# icom_band_decoder.net
KiCad netlist of a schematic drawn in EAGLE
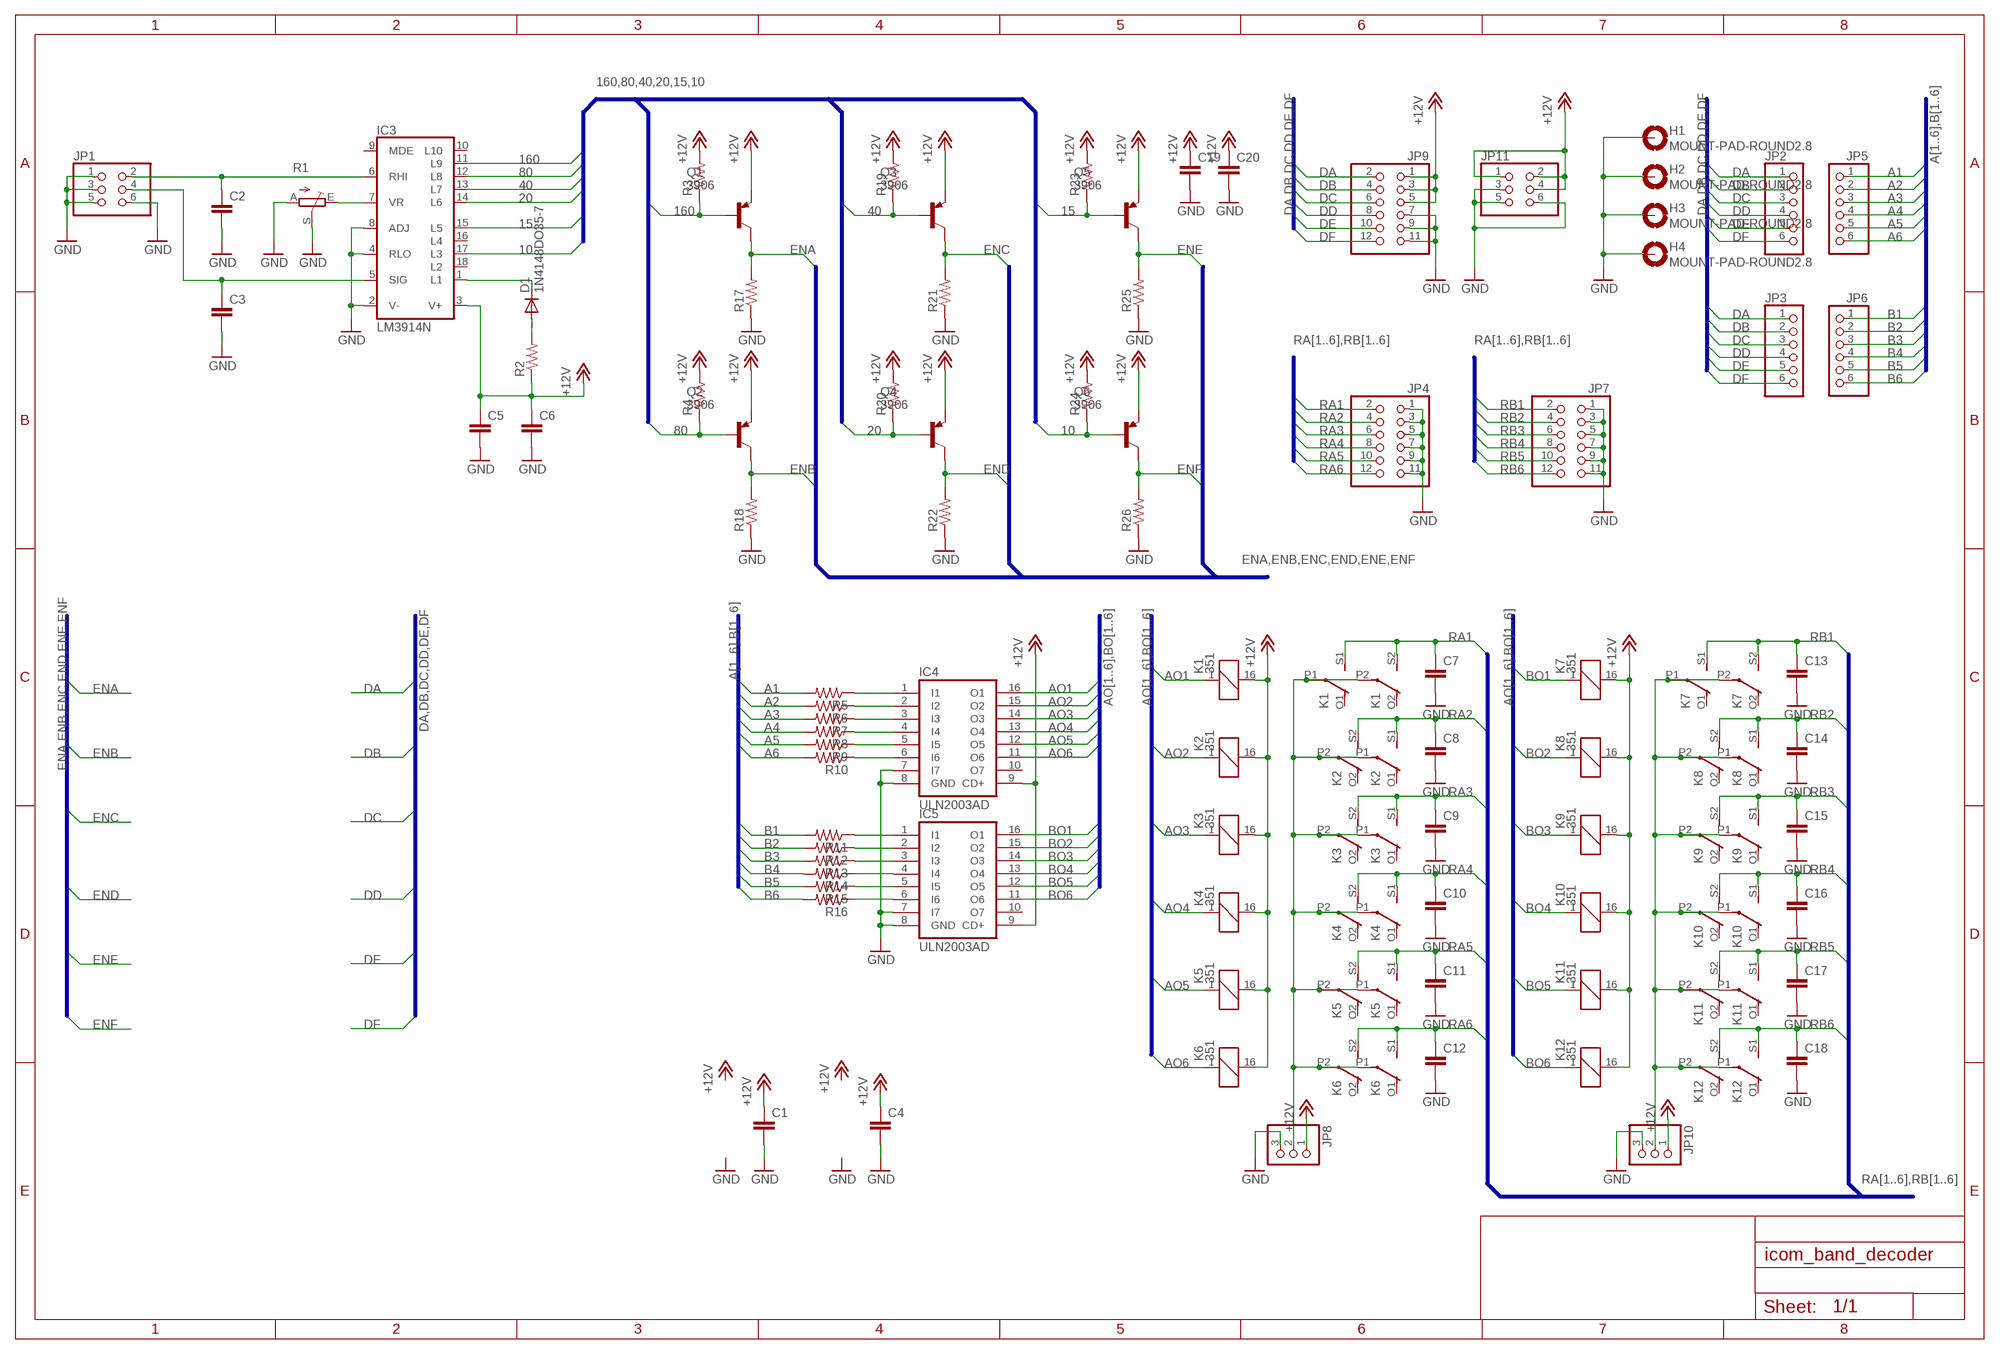
[diagram p0: schematic, sheet 1]

(export (version "E")
  (design (tool "Eeschema 10.0.6"))
  (components
    (comp (ref "C1")
      (value "C-EU050-024X044")
      (footprint "eagle-import:C050-024X044")
      (libsource (lib "eagle-import") (part "C-EU050-024X044"))
    )
    (comp (ref "C2")
      (value "C-EUC0805K")
      (footprint "eagle-import:C0805K")
      (libsource (lib "eagle-import") (part "C-EUC0805K"))
    )
    (comp (ref "C3")
      (value "C-EUC0805K")
      (footprint "eagle-import:C0805K")
      (libsource (lib "eagle-import") (part "C-EUC0805K"))
    )
    (comp (ref "C4")
      (value "C-EU050-024X044")
      (footprint "eagle-import:C050-024X044")
      (libsource (lib "eagle-import") (part "C-EU050-024X044"))
    )
    (comp (ref "C5")
      (value "C-EUC0805K")
      (footprint "eagle-import:C0805K")
      (libsource (lib "eagle-import") (part "C-EUC0805K"))
    )
    (comp (ref "C6")
      (value "C-EU050-024X044")
      (footprint "eagle-import:C050-024X044")
      (libsource (lib "eagle-import") (part "C-EU050-024X044"))
    )
    (comp (ref "C7")
      (value "C-EU050-024X044")
      (footprint "eagle-import:C050-024X044")
      (libsource (lib "eagle-import") (part "C-EU050-024X044"))
    )
    (comp (ref "C8")
      (value "C-EU050-024X044")
      (footprint "eagle-import:C050-024X044")
      (libsource (lib "eagle-import") (part "C-EU050-024X044"))
    )
    (comp (ref "C9")
      (value "C-EU050-024X044")
      (footprint "eagle-import:C050-024X044")
      (libsource (lib "eagle-import") (part "C-EU050-024X044"))
    )
    (comp (ref "C10")
      (value "C-EU050-024X044")
      (footprint "eagle-import:C050-024X044")
      (libsource (lib "eagle-import") (part "C-EU050-024X044"))
    )
    (comp (ref "C11")
      (value "C-EU050-024X044")
      (footprint "eagle-import:C050-024X044")
      (libsource (lib "eagle-import") (part "C-EU050-024X044"))
    )
    (comp (ref "C12")
      (value "C-EU050-024X044")
      (footprint "eagle-import:C050-024X044")
      (libsource (lib "eagle-import") (part "C-EU050-024X044"))
    )
    (comp (ref "C13")
      (value "C-EU050-024X044")
      (footprint "eagle-import:C050-024X044")
      (libsource (lib "eagle-import") (part "C-EU050-024X044"))
    )
    (comp (ref "C14")
      (value "C-EU050-024X044")
      (footprint "eagle-import:C050-024X044")
      (libsource (lib "eagle-import") (part "C-EU050-024X044"))
    )
    (comp (ref "C15")
      (value "C-EU050-024X044")
      (footprint "eagle-import:C050-024X044")
      (libsource (lib "eagle-import") (part "C-EU050-024X044"))
    )
    (comp (ref "C16")
      (value "C-EU050-024X044")
      (footprint "eagle-import:C050-024X044")
      (libsource (lib "eagle-import") (part "C-EU050-024X044"))
    )
    (comp (ref "C17")
      (value "C-EU050-024X044")
      (footprint "eagle-import:C050-024X044")
      (libsource (lib "eagle-import") (part "C-EU050-024X044"))
    )
    (comp (ref "C18")
      (value "C-EU050-024X044")
      (footprint "eagle-import:C050-024X044")
      (libsource (lib "eagle-import") (part "C-EU050-024X044"))
    )
    (comp (ref "C19")
      (value "C-EU050-024X044")
      (footprint "eagle-import:C050-024X044")
      (libsource (lib "eagle-import") (part "C-EU050-024X044"))
    )
    (comp (ref "C20")
      (value "C-EU050-024X044")
      (footprint "eagle-import:C050-024X044")
      (libsource (lib "eagle-import") (part "C-EU050-024X044"))
    )
    (comp (ref "D1")
      (value "1N4148DO35-7")
      (footprint "eagle-import:DO35-7")
      (libsource (lib "eagle-import") (part "1N4148DO35-7"))
    )
    (comp (ref "H1")
      (value "MOUNT-PAD-ROUND2.8")
      (footprint "eagle-import:2,8-PAD")
      (libsource (lib "eagle-import") (part "MOUNT-PAD-ROUND2.8"))
    )
    (comp (ref "H2")
      (value "MOUNT-PAD-ROUND2.8")
      (footprint "eagle-import:2,8-PAD")
      (libsource (lib "eagle-import") (part "MOUNT-PAD-ROUND2.8"))
    )
    (comp (ref "H3")
      (value "MOUNT-PAD-ROUND2.8")
      (footprint "eagle-import:2,8-PAD")
      (libsource (lib "eagle-import") (part "MOUNT-PAD-ROUND2.8"))
    )
    (comp (ref "H4")
      (value "MOUNT-PAD-ROUND2.8")
      (footprint "eagle-import:2,8-PAD")
      (libsource (lib "eagle-import") (part "MOUNT-PAD-ROUND2.8"))
    )
    (comp (ref "IC3")
      (value "LM3914N")
      (footprint "eagle-import:DIL18")
      (libsource (lib "eagle-import") (part "LM3914N"))
    )
    (comp (ref "IC4")
      (value "ULN2003AD")
      (footprint "eagle-import:SO16")
      (libsource (lib "eagle-import") (part "ULN2003AD"))
    )
    (comp (ref "IC5")
      (value "ULN2003AD")
      (footprint "eagle-import:SO16")
      (libsource (lib "eagle-import") (part "ULN2003AD"))
    )
    (comp (ref "JP1")
      (value "PINHD-2X3")
      (footprint "eagle-import:2X03")
      (libsource (lib "eagle-import") (part "PINHD-2X3"))
    )
    (comp (ref "JP2")
      (value "PINHD-1X6")
      (footprint "eagle-import:1X06")
      (libsource (lib "eagle-import") (part "PINHD-1X6"))
    )
    (comp (ref "JP3")
      (value "PINHD-1X6")
      (footprint "eagle-import:1X06")
      (libsource (lib "eagle-import") (part "PINHD-1X6"))
    )
    (comp (ref "JP4")
      (value "PINHD-2X6")
      (footprint "eagle-import:2X06")
      (libsource (lib "eagle-import") (part "PINHD-2X6"))
    )
    (comp (ref "JP5")
      (value "PINHD-1X6")
      (footprint "eagle-import:1X06")
      (libsource (lib "eagle-import") (part "PINHD-1X6"))
    )
    (comp (ref "JP6")
      (value "PINHD-1X6")
      (footprint "eagle-import:1X06")
      (libsource (lib "eagle-import") (part "PINHD-1X6"))
    )
    (comp (ref "JP7")
      (value "PINHD-2X6")
      (footprint "eagle-import:2X06")
      (libsource (lib "eagle-import") (part "PINHD-2X6"))
    )
    (comp (ref "JP8")
      (value "PINHD-1X3")
      (footprint "eagle-import:1X03")
      (libsource (lib "eagle-import") (part "PINHD-1X3"))
    )
    (comp (ref "JP9")
      (value "PINHD-2X6")
      (footprint "eagle-import:2X06")
      (libsource (lib "eagle-import") (part "PINHD-2X6"))
    )
    (comp (ref "JP10")
      (value "PINHD-1X3")
      (footprint "eagle-import:1X03")
      (libsource (lib "eagle-import") (part "PINHD-1X3"))
    )
    (comp (ref "JP11")
      (value "PINHD-2X3")
      (footprint "eagle-import:2X03")
      (libsource (lib "eagle-import") (part "PINHD-2X3"))
    )
    (comp (ref "K1")
      (value "351")
      (footprint "eagle-import:351")
      (libsource (lib "eagle-import") (part "351"))
    )
    (comp (ref "K2")
      (value "351")
      (footprint "eagle-import:351")
      (libsource (lib "eagle-import") (part "351"))
    )
    (comp (ref "K3")
      (value "351")
      (footprint "eagle-import:351")
      (libsource (lib "eagle-import") (part "351"))
    )
    (comp (ref "K4")
      (value "351")
      (footprint "eagle-import:351")
      (libsource (lib "eagle-import") (part "351"))
    )
    (comp (ref "K5")
      (value "351")
      (footprint "eagle-import:351")
      (libsource (lib "eagle-import") (part "351"))
    )
    (comp (ref "K6")
      (value "351")
      (footprint "eagle-import:351")
      (libsource (lib "eagle-import") (part "351"))
    )
    (comp (ref "K7")
      (value "351")
      (footprint "eagle-import:351")
      (libsource (lib "eagle-import") (part "351"))
    )
    (comp (ref "K8")
      (value "351")
      (footprint "eagle-import:351")
      (libsource (lib "eagle-import") (part "351"))
    )
    (comp (ref "K9")
      (value "351")
      (footprint "eagle-import:351")
      (libsource (lib "eagle-import") (part "351"))
    )
    (comp (ref "K10")
      (value "351")
      (footprint "eagle-import:351")
      (libsource (lib "eagle-import") (part "351"))
    )
    (comp (ref "K11")
      (value "351")
      (footprint "eagle-import:351")
      (libsource (lib "eagle-import") (part "351"))
    )
    (comp (ref "K12")
      (value "351")
      (footprint "eagle-import:351")
      (libsource (lib "eagle-import") (part "351"))
    )
    (comp (ref "Q1")
      (value "3906")
      (footprint "eagle-import:SOT23-BEC")
      (libsource (lib "eagle-import") (part "MMBT3906SMDLT1"))
    )
    (comp (ref "Q2")
      (value "3906")
      (footprint "eagle-import:SOT23-BEC")
      (libsource (lib "eagle-import") (part "MMBT3906SMDLT1"))
    )
    (comp (ref "Q3")
      (value "3906")
      (footprint "eagle-import:SOT23-BEC")
      (libsource (lib "eagle-import") (part "MMBT3906SMDLT1"))
    )
    (comp (ref "Q4")
      (value "3906")
      (footprint "eagle-import:SOT23-BEC")
      (libsource (lib "eagle-import") (part "MMBT3906SMDLT1"))
    )
    (comp (ref "Q5")
      (value "3906")
      (footprint "eagle-import:SOT23-BEC")
      (libsource (lib "eagle-import") (part "MMBT3906SMDLT1"))
    )
    (comp (ref "Q6")
      (value "3906")
      (footprint "eagle-import:SOT23-BEC")
      (libsource (lib "eagle-import") (part "MMBT3906SMDLT1"))
    )
    (comp (ref "R1")
      (value "TRIM_EU-CA6V")
      (footprint "eagle-import:CA6V")
      (libsource (lib "eagle-import") (part "TRIM_EU-CA6V"))
    )
    (comp (ref "R2")
      (value "R-US_M0805")
      (footprint "eagle-import:M0805")
      (libsource (lib "eagle-import") (part "R-US_M0805"))
    )
    (comp (ref "R3")
      (value "R-US_M0805")
      (footprint "eagle-import:M0805")
      (libsource (lib "eagle-import") (part "R-US_M0805"))
    )
    (comp (ref "R4")
      (value "R-US_M0805")
      (footprint "eagle-import:M0805")
      (libsource (lib "eagle-import") (part "R-US_M0805"))
    )
    (comp (ref "R5")
      (value "R-US_M0805")
      (footprint "eagle-import:M0805")
      (libsource (lib "eagle-import") (part "R-US_M0805"))
    )
    (comp (ref "R6")
      (value "R-US_M0805")
      (footprint "eagle-import:M0805")
      (libsource (lib "eagle-import") (part "R-US_M0805"))
    )
    (comp (ref "R7")
      (value "R-US_M0805")
      (footprint "eagle-import:M0805")
      (libsource (lib "eagle-import") (part "R-US_M0805"))
    )
    (comp (ref "R8")
      (value "R-US_M0805")
      (footprint "eagle-import:M0805")
      (libsource (lib "eagle-import") (part "R-US_M0805"))
    )
    (comp (ref "R9")
      (value "R-US_M0805")
      (footprint "eagle-import:M0805")
      (libsource (lib "eagle-import") (part "R-US_M0805"))
    )
    (comp (ref "R10")
      (value "R-US_M0805")
      (footprint "eagle-import:M0805")
      (libsource (lib "eagle-import") (part "R-US_M0805"))
    )
    (comp (ref "R11")
      (value "R-US_M0805")
      (footprint "eagle-import:M0805")
      (libsource (lib "eagle-import") (part "R-US_M0805"))
    )
    (comp (ref "R12")
      (value "R-US_M0805")
      (footprint "eagle-import:M0805")
      (libsource (lib "eagle-import") (part "R-US_M0805"))
    )
    (comp (ref "R13")
      (value "R-US_M0805")
      (footprint "eagle-import:M0805")
      (libsource (lib "eagle-import") (part "R-US_M0805"))
    )
    (comp (ref "R14")
      (value "R-US_M0805")
      (footprint "eagle-import:M0805")
      (libsource (lib "eagle-import") (part "R-US_M0805"))
    )
    (comp (ref "R15")
      (value "R-US_M0805")
      (footprint "eagle-import:M0805")
      (libsource (lib "eagle-import") (part "R-US_M0805"))
    )
    (comp (ref "R16")
      (value "R-US_M0805")
      (footprint "eagle-import:M0805")
      (libsource (lib "eagle-import") (part "R-US_M0805"))
    )
    (comp (ref "R17")
      (value "R-US_M0805")
      (footprint "eagle-import:M0805")
      (libsource (lib "eagle-import") (part "R-US_M0805"))
    )
    (comp (ref "R18")
      (value "R-US_M0805")
      (footprint "eagle-import:M0805")
      (libsource (lib "eagle-import") (part "R-US_M0805"))
    )
    (comp (ref "R19")
      (value "R-US_M0805")
      (footprint "eagle-import:M0805")
      (libsource (lib "eagle-import") (part "R-US_M0805"))
    )
    (comp (ref "R20")
      (value "R-US_M0805")
      (footprint "eagle-import:M0805")
      (libsource (lib "eagle-import") (part "R-US_M0805"))
    )
    (comp (ref "R21")
      (value "R-US_M0805")
      (footprint "eagle-import:M0805")
      (libsource (lib "eagle-import") (part "R-US_M0805"))
    )
    (comp (ref "R22")
      (value "R-US_M0805")
      (footprint "eagle-import:M0805")
      (libsource (lib "eagle-import") (part "R-US_M0805"))
    )
    (comp (ref "R23")
      (value "R-US_M0805")
      (footprint "eagle-import:M0805")
      (libsource (lib "eagle-import") (part "R-US_M0805"))
    )
    (comp (ref "R24")
      (value "R-US_M0805")
      (footprint "eagle-import:M0805")
      (libsource (lib "eagle-import") (part "R-US_M0805"))
    )
    (comp (ref "R25")
      (value "R-US_M0805")
      (footprint "eagle-import:M0805")
      (libsource (lib "eagle-import") (part "R-US_M0805"))
    )
    (comp (ref "R26")
      (value "R-US_M0805")
      (footprint "eagle-import:M0805")
      (libsource (lib "eagle-import") (part "R-US_M0805"))
    )
  )
  (nets
    (net (code "1") (name "+12V") (class "Default")
      (node (ref "C1") (pin "1") (pinfunction "1_1") (pintype "passive"))
      (node (ref "C19") (pin "1") (pinfunction "1_1") (pintype "passive"))
      (node (ref "C20") (pin "1") (pinfunction "1_1") (pintype "passive"))
      (node (ref "C4") (pin "1") (pinfunction "1_1") (pintype "passive"))
      (node (ref "C5") (pin "1") (pinfunction "1_1") (pintype "passive"))
      (node (ref "C6") (pin "1") (pinfunction "1_1") (pintype "passive"))
      (node (ref "IC3") (pin "3") (pinfunction "V+_3") (pintype "power_in"))
      (node (ref "IC4") (pin "9") (pinfunction "CD+_9") (pintype "passive"))
      (node (ref "IC5") (pin "9") (pinfunction "CD+_9") (pintype "passive"))
      (node (ref "JP10") (pin "1") (pinfunction "1_1") (pintype "passive"))
      (node (ref "JP11") (pin "1") (pinfunction "1_1") (pintype "passive"))
      (node (ref "JP11") (pin "2") (pinfunction "2_2") (pintype "passive"))
      (node (ref "JP11") (pin "4") (pinfunction "4_4") (pintype "passive"))
      (node (ref "JP8") (pin "1") (pinfunction "1_1") (pintype "passive"))
      (node (ref "JP9") (pin "1") (pinfunction "1_1") (pintype "passive"))
      (node (ref "JP9") (pin "3") (pinfunction "3_3") (pintype "passive"))
      (node (ref "JP9") (pin "5") (pinfunction "5_5") (pintype "passive"))
      (node (ref "K1") (pin "16") (pinfunction "2_16") (pintype "passive"))
      (node (ref "K10") (pin "16") (pinfunction "2_16") (pintype "passive"))
      (node (ref "K11") (pin "16") (pinfunction "2_16") (pintype "passive"))
      (node (ref "K12") (pin "16") (pinfunction "2_16") (pintype "passive"))
      (node (ref "K2") (pin "16") (pinfunction "2_16") (pintype "passive"))
      (node (ref "K3") (pin "16") (pinfunction "2_16") (pintype "passive"))
      (node (ref "K4") (pin "16") (pinfunction "2_16") (pintype "passive"))
      (node (ref "K5") (pin "16") (pinfunction "2_16") (pintype "passive"))
      (node (ref "K6") (pin "16") (pinfunction "2_16") (pintype "passive"))
      (node (ref "K7") (pin "16") (pinfunction "2_16") (pintype "passive"))
      (node (ref "K8") (pin "16") (pinfunction "2_16") (pintype "passive"))
      (node (ref "K9") (pin "16") (pinfunction "2_16") (pintype "passive"))
      (node (ref "Q1") (pin "E") (pinfunction "E_E") (pintype "passive"))
      (node (ref "Q2") (pin "E") (pinfunction "E_E") (pintype "passive"))
      (node (ref "Q3") (pin "E") (pinfunction "E_E") (pintype "passive"))
      (node (ref "Q4") (pin "E") (pinfunction "E_E") (pintype "passive"))
      (node (ref "Q5") (pin "E") (pinfunction "E_E") (pintype "passive"))
      (node (ref "Q6") (pin "E") (pinfunction "E_E") (pintype "passive"))
      (node (ref "R19") (pin "2") (pinfunction "2_2") (pintype "passive"))
      (node (ref "R2") (pin "1") (pinfunction "1_1") (pintype "passive"))
      (node (ref "R20") (pin "2") (pinfunction "2_2") (pintype "passive"))
      (node (ref "R23") (pin "2") (pinfunction "2_2") (pintype "passive"))
      (node (ref "R24") (pin "2") (pinfunction "2_2") (pintype "passive"))
      (node (ref "R3") (pin "2") (pinfunction "2_2") (pintype "passive"))
      (node (ref "R4") (pin "2") (pinfunction "2_2") (pintype "passive"))
    )
    (net (code "2") (name "/10") (class "Default")
      (node (ref "IC3") (pin "17") (pinfunction "L3_17") (pintype "output"))
      (node (ref "Q6") (pin "B") (pinfunction "B_B") (pintype "passive"))
      (node (ref "R24") (pin "1") (pinfunction "1_1") (pintype "passive"))
    )
    (net (code "3") (name "/15") (class "Default")
      (node (ref "IC3") (pin "15") (pinfunction "L5_15") (pintype "output"))
      (node (ref "Q5") (pin "B") (pinfunction "B_B") (pintype "passive"))
      (node (ref "R23") (pin "1") (pinfunction "1_1") (pintype "passive"))
    )
    (net (code "4") (name "/20") (class "Default")
      (node (ref "IC3") (pin "14") (pinfunction "L6_14") (pintype "output"))
      (node (ref "Q4") (pin "B") (pinfunction "B_B") (pintype "passive"))
      (node (ref "R20") (pin "1") (pinfunction "1_1") (pintype "passive"))
    )
    (net (code "5") (name "/40") (class "Default")
      (node (ref "IC3") (pin "13") (pinfunction "L7_13") (pintype "output"))
      (node (ref "Q3") (pin "B") (pinfunction "B_B") (pintype "passive"))
      (node (ref "R19") (pin "1") (pinfunction "1_1") (pintype "passive"))
    )
    (net (code "6") (name "/80") (class "Default")
      (node (ref "IC3") (pin "12") (pinfunction "L8_12") (pintype "output"))
      (node (ref "Q2") (pin "B") (pinfunction "B_B") (pintype "passive"))
      (node (ref "R4") (pin "1") (pinfunction "1_1") (pintype "passive"))
    )
    (net (code "7") (name "/160") (class "Default")
      (node (ref "IC3") (pin "11") (pinfunction "L9_11") (pintype "output"))
      (node (ref "Q1") (pin "B") (pinfunction "B_B") (pintype "passive"))
      (node (ref "R3") (pin "1") (pinfunction "1_1") (pintype "passive"))
    )
    (net (code "8") (name "/A1") (class "Default")
      (node (ref "JP5") (pin "1") (pinfunction "1_1") (pintype "passive"))
      (node (ref "R5") (pin "2") (pinfunction "2_2") (pintype "passive"))
    )
    (net (code "9") (name "/A2") (class "Default")
      (node (ref "JP5") (pin "2") (pinfunction "2_2") (pintype "passive"))
      (node (ref "R6") (pin "2") (pinfunction "2_2") (pintype "passive"))
    )
    (net (code "10") (name "/A3") (class "Default")
      (node (ref "JP5") (pin "3") (pinfunction "3_3") (pintype "passive"))
      (node (ref "R7") (pin "2") (pinfunction "2_2") (pintype "passive"))
    )
    (net (code "11") (name "/A4") (class "Default")
      (node (ref "JP5") (pin "4") (pinfunction "4_4") (pintype "passive"))
      (node (ref "R8") (pin "2") (pinfunction "2_2") (pintype "passive"))
    )
    (net (code "12") (name "/A5") (class "Default")
      (node (ref "JP5") (pin "5") (pinfunction "5_5") (pintype "passive"))
      (node (ref "R9") (pin "2") (pinfunction "2_2") (pintype "passive"))
    )
    (net (code "13") (name "/A6") (class "Default")
      (node (ref "JP5") (pin "6") (pinfunction "6_6") (pintype "passive"))
      (node (ref "R10") (pin "2") (pinfunction "2_2") (pintype "passive"))
    )
    (net (code "14") (name "/AO1") (class "Default")
      (node (ref "IC4") (pin "16") (pinfunction "O1_16") (pintype "open_collector"))
      (node (ref "K1") (pin "1") (pinfunction "1_1") (pintype "passive"))
    )
    (net (code "15") (name "/AO2") (class "Default")
      (node (ref "IC4") (pin "15") (pinfunction "O2_15") (pintype "open_collector"))
      (node (ref "K2") (pin "1") (pinfunction "1_1") (pintype "passive"))
    )
    (net (code "16") (name "/AO3") (class "Default")
      (node (ref "IC4") (pin "14") (pinfunction "O3_14") (pintype "open_collector"))
      (node (ref "K3") (pin "1") (pinfunction "1_1") (pintype "passive"))
    )
    (net (code "17") (name "/AO4") (class "Default")
      (node (ref "IC4") (pin "13") (pinfunction "O4_13") (pintype "open_collector"))
      (node (ref "K4") (pin "1") (pinfunction "1_1") (pintype "passive"))
    )
    (net (code "18") (name "/AO5") (class "Default")
      (node (ref "IC4") (pin "12") (pinfunction "O5_12") (pintype "open_collector"))
      (node (ref "K5") (pin "1") (pinfunction "1_1") (pintype "passive"))
    )
    (net (code "19") (name "/AO6") (class "Default")
      (node (ref "IC4") (pin "11") (pinfunction "O6_11") (pintype "open_collector"))
      (node (ref "K6") (pin "1") (pinfunction "1_1") (pintype "passive"))
    )
    (net (code "20") (name "/B1") (class "Default")
      (node (ref "JP6") (pin "1") (pinfunction "1_1") (pintype "passive"))
      (node (ref "R11") (pin "2") (pinfunction "2_2") (pintype "passive"))
    )
    (net (code "21") (name "/B2") (class "Default")
      (node (ref "JP6") (pin "2") (pinfunction "2_2") (pintype "passive"))
      (node (ref "R12") (pin "2") (pinfunction "2_2") (pintype "passive"))
    )
    (net (code "22") (name "/B3") (class "Default")
      (node (ref "JP6") (pin "3") (pinfunction "3_3") (pintype "passive"))
      (node (ref "R13") (pin "2") (pinfunction "2_2") (pintype "passive"))
    )
    (net (code "23") (name "/B4") (class "Default")
      (node (ref "JP6") (pin "4") (pinfunction "4_4") (pintype "passive"))
      (node (ref "R14") (pin "2") (pinfunction "2_2") (pintype "passive"))
    )
    (net (code "24") (name "/B5") (class "Default")
      (node (ref "JP6") (pin "5") (pinfunction "5_5") (pintype "passive"))
      (node (ref "R15") (pin "2") (pinfunction "2_2") (pintype "passive"))
    )
    (net (code "25") (name "/B6") (class "Default")
      (node (ref "JP6") (pin "6") (pinfunction "6_6") (pintype "passive"))
      (node (ref "R16") (pin "2") (pinfunction "2_2") (pintype "passive"))
    )
    (net (code "26") (name "/BO1") (class "Default")
      (node (ref "IC5") (pin "16") (pinfunction "O1_16") (pintype "open_collector"))
      (node (ref "K7") (pin "1") (pinfunction "1_1") (pintype "passive"))
    )
    (net (code "27") (name "/BO2") (class "Default")
      (node (ref "IC5") (pin "15") (pinfunction "O2_15") (pintype "open_collector"))
      (node (ref "K8") (pin "1") (pinfunction "1_1") (pintype "passive"))
    )
    (net (code "28") (name "/BO3") (class "Default")
      (node (ref "IC5") (pin "14") (pinfunction "O3_14") (pintype "open_collector"))
      (node (ref "K9") (pin "1") (pinfunction "1_1") (pintype "passive"))
    )
    (net (code "29") (name "/BO4") (class "Default")
      (node (ref "IC5") (pin "13") (pinfunction "O4_13") (pintype "open_collector"))
      (node (ref "K10") (pin "1") (pinfunction "1_1") (pintype "passive"))
    )
    (net (code "30") (name "/BO5") (class "Default")
      (node (ref "IC5") (pin "12") (pinfunction "O5_12") (pintype "open_collector"))
      (node (ref "K11") (pin "1") (pinfunction "1_1") (pintype "passive"))
    )
    (net (code "31") (name "/BO6") (class "Default")
      (node (ref "IC5") (pin "11") (pinfunction "O6_11") (pintype "open_collector"))
      (node (ref "K12") (pin "1") (pinfunction "1_1") (pintype "passive"))
    )
    (net (code "32") (name "/DA") (class "Default")
      (node (ref "JP2") (pin "1") (pinfunction "1_1") (pintype "passive"))
      (node (ref "JP3") (pin "1") (pinfunction "1_1") (pintype "passive"))
      (node (ref "JP9") (pin "2") (pinfunction "2_2") (pintype "passive"))
    )
    (net (code "33") (name "/DB") (class "Default")
      (node (ref "JP2") (pin "2") (pinfunction "2_2") (pintype "passive"))
      (node (ref "JP3") (pin "2") (pinfunction "2_2") (pintype "passive"))
      (node (ref "JP9") (pin "4") (pinfunction "4_4") (pintype "passive"))
    )
    (net (code "34") (name "/DC") (class "Default")
      (node (ref "JP2") (pin "3") (pinfunction "3_3") (pintype "passive"))
      (node (ref "JP3") (pin "3") (pinfunction "3_3") (pintype "passive"))
      (node (ref "JP9") (pin "6") (pinfunction "6_6") (pintype "passive"))
    )
    (net (code "35") (name "/DD") (class "Default")
      (node (ref "JP2") (pin "4") (pinfunction "4_4") (pintype "passive"))
      (node (ref "JP3") (pin "4") (pinfunction "4_4") (pintype "passive"))
      (node (ref "JP9") (pin "8") (pinfunction "8_8") (pintype "passive"))
    )
    (net (code "36") (name "/DE") (class "Default")
      (node (ref "JP2") (pin "5") (pinfunction "5_5") (pintype "passive"))
      (node (ref "JP3") (pin "5") (pinfunction "5_5") (pintype "passive"))
      (node (ref "JP9") (pin "10") (pinfunction "10_10") (pintype "passive"))
    )
    (net (code "37") (name "/DF") (class "Default")
      (node (ref "JP2") (pin "6") (pinfunction "6_6") (pintype "passive"))
      (node (ref "JP3") (pin "6") (pinfunction "6_6") (pintype "passive"))
      (node (ref "JP9") (pin "12") (pinfunction "12_12") (pintype "passive"))
    )
    (net (code "38") (name "/ENA") (class "Default")
      (node (ref "Q1") (pin "C") (pinfunction "C_C") (pintype "passive"))
      (node (ref "R17") (pin "2") (pinfunction "2_2") (pintype "passive"))
    )
    (net (code "39") (name "/ENB") (class "Default")
      (node (ref "Q2") (pin "C") (pinfunction "C_C") (pintype "passive"))
      (node (ref "R18") (pin "2") (pinfunction "2_2") (pintype "passive"))
    )
    (net (code "40") (name "/ENC") (class "Default")
      (node (ref "Q3") (pin "C") (pinfunction "C_C") (pintype "passive"))
      (node (ref "R21") (pin "2") (pinfunction "2_2") (pintype "passive"))
    )
    (net (code "41") (name "/END") (class "Default")
      (node (ref "Q4") (pin "C") (pinfunction "C_C") (pintype "passive"))
      (node (ref "R22") (pin "2") (pinfunction "2_2") (pintype "passive"))
    )
    (net (code "42") (name "/ENE") (class "Default")
      (node (ref "Q5") (pin "C") (pinfunction "C_C") (pintype "passive"))
      (node (ref "R25") (pin "2") (pinfunction "2_2") (pintype "passive"))
    )
    (net (code "43") (name "/ENF") (class "Default")
      (node (ref "Q6") (pin "C") (pinfunction "C_C") (pintype "passive"))
      (node (ref "R26") (pin "2") (pinfunction "2_2") (pintype "passive"))
    )
    (net (code "44") (name "/RA1") (class "Default")
      (node (ref "C7") (pin "1") (pinfunction "1_1") (pintype "passive"))
      (node (ref "JP4") (pin "2") (pinfunction "2_2") (pintype "passive"))
      (node (ref "K1") (pin "S1") (pinfunction "S_S1") (pintype "passive"))
      (node (ref "K1") (pin "S2") (pinfunction "S_S2") (pintype "passive"))
    )
    (net (code "45") (name "/RA2") (class "Default")
      (node (ref "C8") (pin "1") (pinfunction "1_1") (pintype "passive"))
      (node (ref "JP4") (pin "4") (pinfunction "4_4") (pintype "passive"))
      (node (ref "K2") (pin "S1") (pinfunction "S_S1") (pintype "passive"))
      (node (ref "K2") (pin "S2") (pinfunction "S_S2") (pintype "passive"))
    )
    (net (code "46") (name "/RA3") (class "Default")
      (node (ref "C9") (pin "1") (pinfunction "1_1") (pintype "passive"))
      (node (ref "JP4") (pin "6") (pinfunction "6_6") (pintype "passive"))
      (node (ref "K3") (pin "S1") (pinfunction "S_S1") (pintype "passive"))
      (node (ref "K3") (pin "S2") (pinfunction "S_S2") (pintype "passive"))
    )
    (net (code "47") (name "/RA4") (class "Default")
      (node (ref "C10") (pin "1") (pinfunction "1_1") (pintype "passive"))
      (node (ref "JP4") (pin "8") (pinfunction "8_8") (pintype "passive"))
      (node (ref "K4") (pin "S1") (pinfunction "S_S1") (pintype "passive"))
      (node (ref "K4") (pin "S2") (pinfunction "S_S2") (pintype "passive"))
    )
    (net (code "48") (name "/RA5") (class "Default")
      (node (ref "C11") (pin "1") (pinfunction "1_1") (pintype "passive"))
      (node (ref "JP4") (pin "10") (pinfunction "10_10") (pintype "passive"))
      (node (ref "K5") (pin "S1") (pinfunction "S_S1") (pintype "passive"))
      (node (ref "K5") (pin "S2") (pinfunction "S_S2") (pintype "passive"))
    )
    (net (code "49") (name "/RA6") (class "Default")
      (node (ref "C12") (pin "1") (pinfunction "1_1") (pintype "passive"))
      (node (ref "JP4") (pin "12") (pinfunction "12_12") (pintype "passive"))
      (node (ref "K6") (pin "S1") (pinfunction "S_S1") (pintype "passive"))
      (node (ref "K6") (pin "S2") (pinfunction "S_S2") (pintype "passive"))
    )
    (net (code "50") (name "/RB1") (class "Default")
      (node (ref "C13") (pin "1") (pinfunction "1_1") (pintype "passive"))
      (node (ref "JP7") (pin "2") (pinfunction "2_2") (pintype "passive"))
      (node (ref "K7") (pin "S1") (pinfunction "S_S1") (pintype "passive"))
      (node (ref "K7") (pin "S2") (pinfunction "S_S2") (pintype "passive"))
    )
    (net (code "51") (name "/RB2") (class "Default")
      (node (ref "C14") (pin "1") (pinfunction "1_1") (pintype "passive"))
      (node (ref "JP7") (pin "4") (pinfunction "4_4") (pintype "passive"))
      (node (ref "K8") (pin "S1") (pinfunction "S_S1") (pintype "passive"))
      (node (ref "K8") (pin "S2") (pinfunction "S_S2") (pintype "passive"))
    )
    (net (code "52") (name "/RB3") (class "Default")
      (node (ref "C15") (pin "1") (pinfunction "1_1") (pintype "passive"))
      (node (ref "JP7") (pin "6") (pinfunction "6_6") (pintype "passive"))
      (node (ref "K9") (pin "S1") (pinfunction "S_S1") (pintype "passive"))
      (node (ref "K9") (pin "S2") (pinfunction "S_S2") (pintype "passive"))
    )
    (net (code "53") (name "/RB4") (class "Default")
      (node (ref "C16") (pin "1") (pinfunction "1_1") (pintype "passive"))
      (node (ref "JP7") (pin "8") (pinfunction "8_8") (pintype "passive"))
      (node (ref "K10") (pin "S1") (pinfunction "S_S1") (pintype "passive"))
      (node (ref "K10") (pin "S2") (pinfunction "S_S2") (pintype "passive"))
    )
    (net (code "54") (name "/RB5") (class "Default")
      (node (ref "C17") (pin "1") (pinfunction "1_1") (pintype "passive"))
      (node (ref "JP7") (pin "10") (pinfunction "10_10") (pintype "passive"))
      (node (ref "K11") (pin "S1") (pinfunction "S_S1") (pintype "passive"))
      (node (ref "K11") (pin "S2") (pinfunction "S_S2") (pintype "passive"))
    )
    (net (code "55") (name "/RB6") (class "Default")
      (node (ref "C18") (pin "1") (pinfunction "1_1") (pintype "passive"))
      (node (ref "JP7") (pin "12") (pinfunction "12_12") (pintype "passive"))
      (node (ref "K12") (pin "S1") (pinfunction "S_S1") (pintype "passive"))
      (node (ref "K12") (pin "S2") (pinfunction "S_S2") (pintype "passive"))
    )
    (net (code "62") (name "GND") (class "Default")
      (node (ref "C1") (pin "2") (pinfunction "2_2") (pintype "passive"))
      (node (ref "C10") (pin "2") (pinfunction "2_2") (pintype "passive"))
      (node (ref "C11") (pin "2") (pinfunction "2_2") (pintype "passive"))
      (node (ref "C12") (pin "2") (pinfunction "2_2") (pintype "passive"))
      (node (ref "C13") (pin "2") (pinfunction "2_2") (pintype "passive"))
      (node (ref "C14") (pin "2") (pinfunction "2_2") (pintype "passive"))
      (node (ref "C15") (pin "2") (pinfunction "2_2") (pintype "passive"))
      (node (ref "C16") (pin "2") (pinfunction "2_2") (pintype "passive"))
      (node (ref "C17") (pin "2") (pinfunction "2_2") (pintype "passive"))
      (node (ref "C18") (pin "2") (pinfunction "2_2") (pintype "passive"))
      (node (ref "C19") (pin "2") (pinfunction "2_2") (pintype "passive"))
      (node (ref "C2") (pin "2") (pinfunction "2_2") (pintype "passive"))
      (node (ref "C20") (pin "2") (pinfunction "2_2") (pintype "passive"))
      (node (ref "C3") (pin "2") (pinfunction "2_2") (pintype "passive"))
      (node (ref "C4") (pin "2") (pinfunction "2_2") (pintype "passive"))
      (node (ref "C5") (pin "2") (pinfunction "2_2") (pintype "passive"))
      (node (ref "C6") (pin "2") (pinfunction "2_2") (pintype "passive"))
      (node (ref "C7") (pin "2") (pinfunction "2_2") (pintype "passive"))
      (node (ref "C8") (pin "2") (pinfunction "2_2") (pintype "passive"))
      (node (ref "C9") (pin "2") (pinfunction "2_2") (pintype "passive"))
      (node (ref "H1") (pin "B2,8") (pinfunction "MOUNT_B2,8") (pintype "passive"))
      (node (ref "H2") (pin "B2,8") (pinfunction "MOUNT_B2,8") (pintype "passive"))
      (node (ref "H3") (pin "B2,8") (pinfunction "MOUNT_B2,8") (pintype "passive"))
      (node (ref "H4") (pin "B2,8") (pinfunction "MOUNT_B2,8") (pintype "passive"))
      (node (ref "IC3") (pin "2") (pinfunction "V-_2") (pintype "power_in"))
      (node (ref "IC3") (pin "4") (pinfunction "RLO_4") (pintype "input"))
      (node (ref "IC3") (pin "8") (pinfunction "ADJ_8") (pintype "input"))
      (node (ref "IC4") (pin "7") (pinfunction "I7_7") (pintype "input"))
      (node (ref "IC4") (pin "8") (pinfunction "GND_8") (pintype "power_in"))
      (node (ref "IC5") (pin "7") (pinfunction "I7_7") (pintype "input"))
      (node (ref "IC5") (pin "8") (pinfunction "GND_8") (pintype "power_in"))
      (node (ref "JP1") (pin "1") (pinfunction "1_1") (pintype "passive"))
      (node (ref "JP1") (pin "3") (pinfunction "3_3") (pintype "passive"))
      (node (ref "JP1") (pin "5") (pinfunction "5_5") (pintype "passive"))
      (node (ref "JP1") (pin "6") (pinfunction "6_6") (pintype "passive"))
      (node (ref "JP10") (pin "3") (pinfunction "3_3") (pintype "passive"))
      (node (ref "JP11") (pin "3") (pinfunction "3_3") (pintype "passive"))
      (node (ref "JP11") (pin "5") (pinfunction "5_5") (pintype "passive"))
      (node (ref "JP11") (pin "6") (pinfunction "6_6") (pintype "passive"))
      (node (ref "JP4") (pin "1") (pinfunction "1_1") (pintype "passive"))
      (node (ref "JP4") (pin "11") (pinfunction "11_11") (pintype "passive"))
      (node (ref "JP4") (pin "3") (pinfunction "3_3") (pintype "passive"))
      (node (ref "JP4") (pin "5") (pinfunction "5_5") (pintype "passive"))
      (node (ref "JP4") (pin "7") (pinfunction "7_7") (pintype "passive"))
      (node (ref "JP4") (pin "9") (pinfunction "9_9") (pintype "passive"))
      (node (ref "JP7") (pin "1") (pinfunction "1_1") (pintype "passive"))
      (node (ref "JP7") (pin "11") (pinfunction "11_11") (pintype "passive"))
      (node (ref "JP7") (pin "3") (pinfunction "3_3") (pintype "passive"))
      (node (ref "JP7") (pin "5") (pinfunction "5_5") (pintype "passive"))
      (node (ref "JP7") (pin "7") (pinfunction "7_7") (pintype "passive"))
      (node (ref "JP7") (pin "9") (pinfunction "9_9") (pintype "passive"))
      (node (ref "JP8") (pin "3") (pinfunction "3_3") (pintype "passive"))
      (node (ref "JP9") (pin "11") (pinfunction "11_11") (pintype "passive"))
      (node (ref "JP9") (pin "7") (pinfunction "7_7") (pintype "passive"))
      (node (ref "JP9") (pin "9") (pinfunction "9_9") (pintype "passive"))
      (node (ref "R1") (pin "A") (pinfunction "A_A") (pintype "passive"))
      (node (ref "R1") (pin "S") (pinfunction "S_S") (pintype "passive"))
      (node (ref "R17") (pin "1") (pinfunction "1_1") (pintype "passive"))
      (node (ref "R18") (pin "1") (pinfunction "1_1") (pintype "passive"))
      (node (ref "R21") (pin "1") (pinfunction "1_1") (pintype "passive"))
      (node (ref "R22") (pin "1") (pinfunction "1_1") (pintype "passive"))
      (node (ref "R25") (pin "1") (pinfunction "1_1") (pintype "passive"))
      (node (ref "R26") (pin "1") (pinfunction "1_1") (pintype "passive"))
    )
    (net (code "63") (name "Net-(D1-PadA)") (class "Default")
      (node (ref "D1") (pin "A") (pinfunction "A_A") (pintype "passive"))
      (node (ref "R2") (pin "2") (pinfunction "2_2") (pintype "passive"))
    )
    (net (code "64") (name "Net-(IC3-L1)") (class "Default")
      (node (ref "D1") (pin "C") (pinfunction "C_C") (pintype "passive"))
      (node (ref "IC3") (pin "1") (pinfunction "L1_1") (pintype "output"))
    )
    (net (code "65") (name "Net-(IC3-RHI)") (class "Default")
      (node (ref "C2") (pin "1") (pinfunction "1_1") (pintype "passive"))
      (node (ref "IC3") (pin "6") (pinfunction "RHI_6") (pintype "input"))
      (node (ref "JP1") (pin "2") (pinfunction "2_2") (pintype "passive"))
    )
    (net (code "66") (name "Net-(IC3-SIG)") (class "Default")
      (node (ref "C3") (pin "1") (pinfunction "1_1") (pintype "passive"))
      (node (ref "IC3") (pin "5") (pinfunction "SIG_5") (pintype "input"))
      (node (ref "JP1") (pin "4") (pinfunction "4_4") (pintype "passive"))
    )
    (net (code "67") (name "Net-(IC3-VR)") (class "Default")
      (node (ref "IC3") (pin "7") (pinfunction "VR_7") (pintype "output"))
      (node (ref "R1") (pin "E") (pinfunction "E_E") (pintype "passive"))
    )
    (net (code "68") (name "Net-(IC4-I1)") (class "Default")
      (node (ref "IC4") (pin "1") (pinfunction "I1_1") (pintype "input"))
      (node (ref "R5") (pin "1") (pinfunction "1_1") (pintype "passive"))
    )
    (net (code "69") (name "Net-(IC4-I2)") (class "Default")
      (node (ref "IC4") (pin "2") (pinfunction "I2_2") (pintype "input"))
      (node (ref "R6") (pin "1") (pinfunction "1_1") (pintype "passive"))
    )
    (net (code "70") (name "Net-(IC4-I3)") (class "Default")
      (node (ref "IC4") (pin "3") (pinfunction "I3_3") (pintype "input"))
      (node (ref "R7") (pin "1") (pinfunction "1_1") (pintype "passive"))
    )
    (net (code "71") (name "Net-(IC4-I4)") (class "Default")
      (node (ref "IC4") (pin "4") (pinfunction "I4_4") (pintype "input"))
      (node (ref "R8") (pin "1") (pinfunction "1_1") (pintype "passive"))
    )
    (net (code "72") (name "Net-(IC4-I5)") (class "Default")
      (node (ref "IC4") (pin "5") (pinfunction "I5_5") (pintype "input"))
      (node (ref "R9") (pin "1") (pinfunction "1_1") (pintype "passive"))
    )
    (net (code "73") (name "Net-(IC4-I6)") (class "Default")
      (node (ref "IC4") (pin "6") (pinfunction "I6_6") (pintype "input"))
      (node (ref "R10") (pin "1") (pinfunction "1_1") (pintype "passive"))
    )
    (net (code "74") (name "Net-(IC5-I1)") (class "Default")
      (node (ref "IC5") (pin "1") (pinfunction "I1_1") (pintype "input"))
      (node (ref "R11") (pin "1") (pinfunction "1_1") (pintype "passive"))
    )
    (net (code "75") (name "Net-(IC5-I2)") (class "Default")
      (node (ref "IC5") (pin "2") (pinfunction "I2_2") (pintype "input"))
      (node (ref "R12") (pin "1") (pinfunction "1_1") (pintype "passive"))
    )
    (net (code "76") (name "Net-(IC5-I3)") (class "Default")
      (node (ref "IC5") (pin "3") (pinfunction "I3_3") (pintype "input"))
      (node (ref "R13") (pin "1") (pinfunction "1_1") (pintype "passive"))
    )
    (net (code "77") (name "Net-(IC5-I4)") (class "Default")
      (node (ref "IC5") (pin "4") (pinfunction "I4_4") (pintype "input"))
      (node (ref "R14") (pin "1") (pinfunction "1_1") (pintype "passive"))
    )
    (net (code "78") (name "Net-(IC5-I5)") (class "Default")
      (node (ref "IC5") (pin "5") (pinfunction "I5_5") (pintype "input"))
      (node (ref "R15") (pin "1") (pinfunction "1_1") (pintype "passive"))
    )
    (net (code "79") (name "Net-(IC5-I6)") (class "Default")
      (node (ref "IC5") (pin "6") (pinfunction "I6_6") (pintype "input"))
      (node (ref "R16") (pin "1") (pinfunction "1_1") (pintype "passive"))
    )
    (net (code "80") (name "Net-(K1B-P)") (class "Default")
      (node (ref "JP8") (pin "2") (pinfunction "2_2") (pintype "passive"))
      (node (ref "K1") (pin "P1") (pinfunction "P_P1") (pintype "passive"))
      (node (ref "K1") (pin "P2") (pinfunction "P_P2") (pintype "passive"))
      (node (ref "K2") (pin "P1") (pinfunction "P_P1") (pintype "passive"))
      (node (ref "K2") (pin "P2") (pinfunction "P_P2") (pintype "passive"))
      (node (ref "K3") (pin "P1") (pinfunction "P_P1") (pintype "passive"))
      (node (ref "K3") (pin "P2") (pinfunction "P_P2") (pintype "passive"))
      (node (ref "K4") (pin "P1") (pinfunction "P_P1") (pintype "passive"))
      (node (ref "K4") (pin "P2") (pinfunction "P_P2") (pintype "passive"))
      (node (ref "K5") (pin "P1") (pinfunction "P_P1") (pintype "passive"))
      (node (ref "K5") (pin "P2") (pinfunction "P_P2") (pintype "passive"))
      (node (ref "K6") (pin "P1") (pinfunction "P_P1") (pintype "passive"))
      (node (ref "K6") (pin "P2") (pinfunction "P_P2") (pintype "passive"))
    )
    (net (code "81") (name "Net-(K10B-P)") (class "Default")
      (node (ref "JP10") (pin "2") (pinfunction "2_2") (pintype "passive"))
      (node (ref "K10") (pin "P1") (pinfunction "P_P1") (pintype "passive"))
      (node (ref "K10") (pin "P2") (pinfunction "P_P2") (pintype "passive"))
      (node (ref "K11") (pin "P1") (pinfunction "P_P1") (pintype "passive"))
      (node (ref "K11") (pin "P2") (pinfunction "P_P2") (pintype "passive"))
      (node (ref "K12") (pin "P1") (pinfunction "P_P1") (pintype "passive"))
      (node (ref "K12") (pin "P2") (pinfunction "P_P2") (pintype "passive"))
      (node (ref "K7") (pin "P1") (pinfunction "P_P1") (pintype "passive"))
      (node (ref "K7") (pin "P2") (pinfunction "P_P2") (pintype "passive"))
      (node (ref "K8") (pin "P1") (pinfunction "P_P1") (pintype "passive"))
      (node (ref "K8") (pin "P2") (pinfunction "P_P2") (pintype "passive"))
      (node (ref "K9") (pin "P1") (pinfunction "P_P1") (pintype "passive"))
      (node (ref "K9") (pin "P2") (pinfunction "P_P2") (pintype "passive"))
    )
    (net (code "82") (name "unconnected-(IC3-L2-Pad18)") (class "Default")
      (node (ref "IC3") (pin "18") (pinfunction "L2_18") (pintype "output"))
    )
    (net (code "83") (name "unconnected-(IC3-L4-Pad16)") (class "Default")
      (node (ref "IC3") (pin "16") (pinfunction "L4_16") (pintype "output"))
    )
    (net (code "84") (name "unconnected-(IC3-L10-Pad10)") (class "Default")
      (node (ref "IC3") (pin "10") (pinfunction "L10_10") (pintype "output"))
    )
    (net (code "85") (name "unconnected-(IC3-MDE-Pad9)") (class "Default")
      (node (ref "IC3") (pin "9") (pinfunction "MDE_9") (pintype "input"))
    )
    (net (code "86") (name "unconnected-(IC4-O7-Pad10)") (class "Default")
      (node (ref "IC4") (pin "10") (pinfunction "O7_10") (pintype "open_collector"))
    )
    (net (code "87") (name "unconnected-(IC5-O7-Pad10)") (class "Default")
      (node (ref "IC5") (pin "10") (pinfunction "O7_10") (pintype "open_collector"))
    )
    (net (code "88") (name "unconnected-(K1B-O-PadO1)") (class "Default")
      (node (ref "K1") (pin "O1") (pinfunction "O_O1") (pintype "passive"))
    )
    (net (code "89") (name "unconnected-(K1C-O-PadO2)") (class "Default")
      (node (ref "K1") (pin "O2") (pinfunction "O_O2") (pintype "passive"))
    )
    (net (code "90") (name "unconnected-(K2B-O-PadO1)") (class "Default")
      (node (ref "K2") (pin "O1") (pinfunction "O_O1") (pintype "passive"))
    )
    (net (code "91") (name "unconnected-(K2C-O-PadO2)") (class "Default")
      (node (ref "K2") (pin "O2") (pinfunction "O_O2") (pintype "passive"))
    )
    (net (code "92") (name "unconnected-(K3B-O-PadO1)") (class "Default")
      (node (ref "K3") (pin "O1") (pinfunction "O_O1") (pintype "passive"))
    )
    (net (code "93") (name "unconnected-(K3C-O-PadO2)") (class "Default")
      (node (ref "K3") (pin "O2") (pinfunction "O_O2") (pintype "passive"))
    )
    (net (code "94") (name "unconnected-(K4B-O-PadO1)") (class "Default")
      (node (ref "K4") (pin "O1") (pinfunction "O_O1") (pintype "passive"))
    )
    (net (code "95") (name "unconnected-(K4C-O-PadO2)") (class "Default")
      (node (ref "K4") (pin "O2") (pinfunction "O_O2") (pintype "passive"))
    )
    (net (code "96") (name "unconnected-(K5B-O-PadO1)") (class "Default")
      (node (ref "K5") (pin "O1") (pinfunction "O_O1") (pintype "passive"))
    )
    (net (code "97") (name "unconnected-(K5C-O-PadO2)") (class "Default")
      (node (ref "K5") (pin "O2") (pinfunction "O_O2") (pintype "passive"))
    )
    (net (code "98") (name "unconnected-(K6B-O-PadO1)") (class "Default")
      (node (ref "K6") (pin "O1") (pinfunction "O_O1") (pintype "passive"))
    )
    (net (code "99") (name "unconnected-(K6C-O-PadO2)") (class "Default")
      (node (ref "K6") (pin "O2") (pinfunction "O_O2") (pintype "passive"))
    )
    (net (code "100") (name "unconnected-(K7B-O-PadO1)") (class "Default")
      (node (ref "K7") (pin "O1") (pinfunction "O_O1") (pintype "passive"))
    )
    (net (code "101") (name "unconnected-(K7C-O-PadO2)") (class "Default")
      (node (ref "K7") (pin "O2") (pinfunction "O_O2") (pintype "passive"))
    )
    (net (code "102") (name "unconnected-(K8B-O-PadO1)") (class "Default")
      (node (ref "K8") (pin "O1") (pinfunction "O_O1") (pintype "passive"))
    )
    (net (code "103") (name "unconnected-(K8C-O-PadO2)") (class "Default")
      (node (ref "K8") (pin "O2") (pinfunction "O_O2") (pintype "passive"))
    )
    (net (code "104") (name "unconnected-(K9B-O-PadO1)") (class "Default")
      (node (ref "K9") (pin "O1") (pinfunction "O_O1") (pintype "passive"))
    )
    (net (code "105") (name "unconnected-(K9C-O-PadO2)") (class "Default")
      (node (ref "K9") (pin "O2") (pinfunction "O_O2") (pintype "passive"))
    )
    (net (code "106") (name "unconnected-(K10B-O-PadO1)") (class "Default")
      (node (ref "K10") (pin "O1") (pinfunction "O_O1") (pintype "passive"))
    )
    (net (code "107") (name "unconnected-(K10C-O-PadO2)") (class "Default")
      (node (ref "K10") (pin "O2") (pinfunction "O_O2") (pintype "passive"))
    )
    (net (code "108") (name "unconnected-(K11B-O-PadO1)") (class "Default")
      (node (ref "K11") (pin "O1") (pinfunction "O_O1") (pintype "passive"))
    )
    (net (code "109") (name "unconnected-(K11C-O-PadO2)") (class "Default")
      (node (ref "K11") (pin "O2") (pinfunction "O_O2") (pintype "passive"))
    )
    (net (code "110") (name "unconnected-(K12B-O-PadO1)") (class "Default")
      (node (ref "K12") (pin "O1") (pinfunction "O_O1") (pintype "passive"))
    )
    (net (code "111") (name "unconnected-(K12C-O-PadO2)") (class "Default")
      (node (ref "K12") (pin "O2") (pinfunction "O_O2") (pintype "passive"))
    )
  )
)
